# GTU-2-V1_1-20160516.net
KiCad netlist of a schematic drawn in Altium Designer
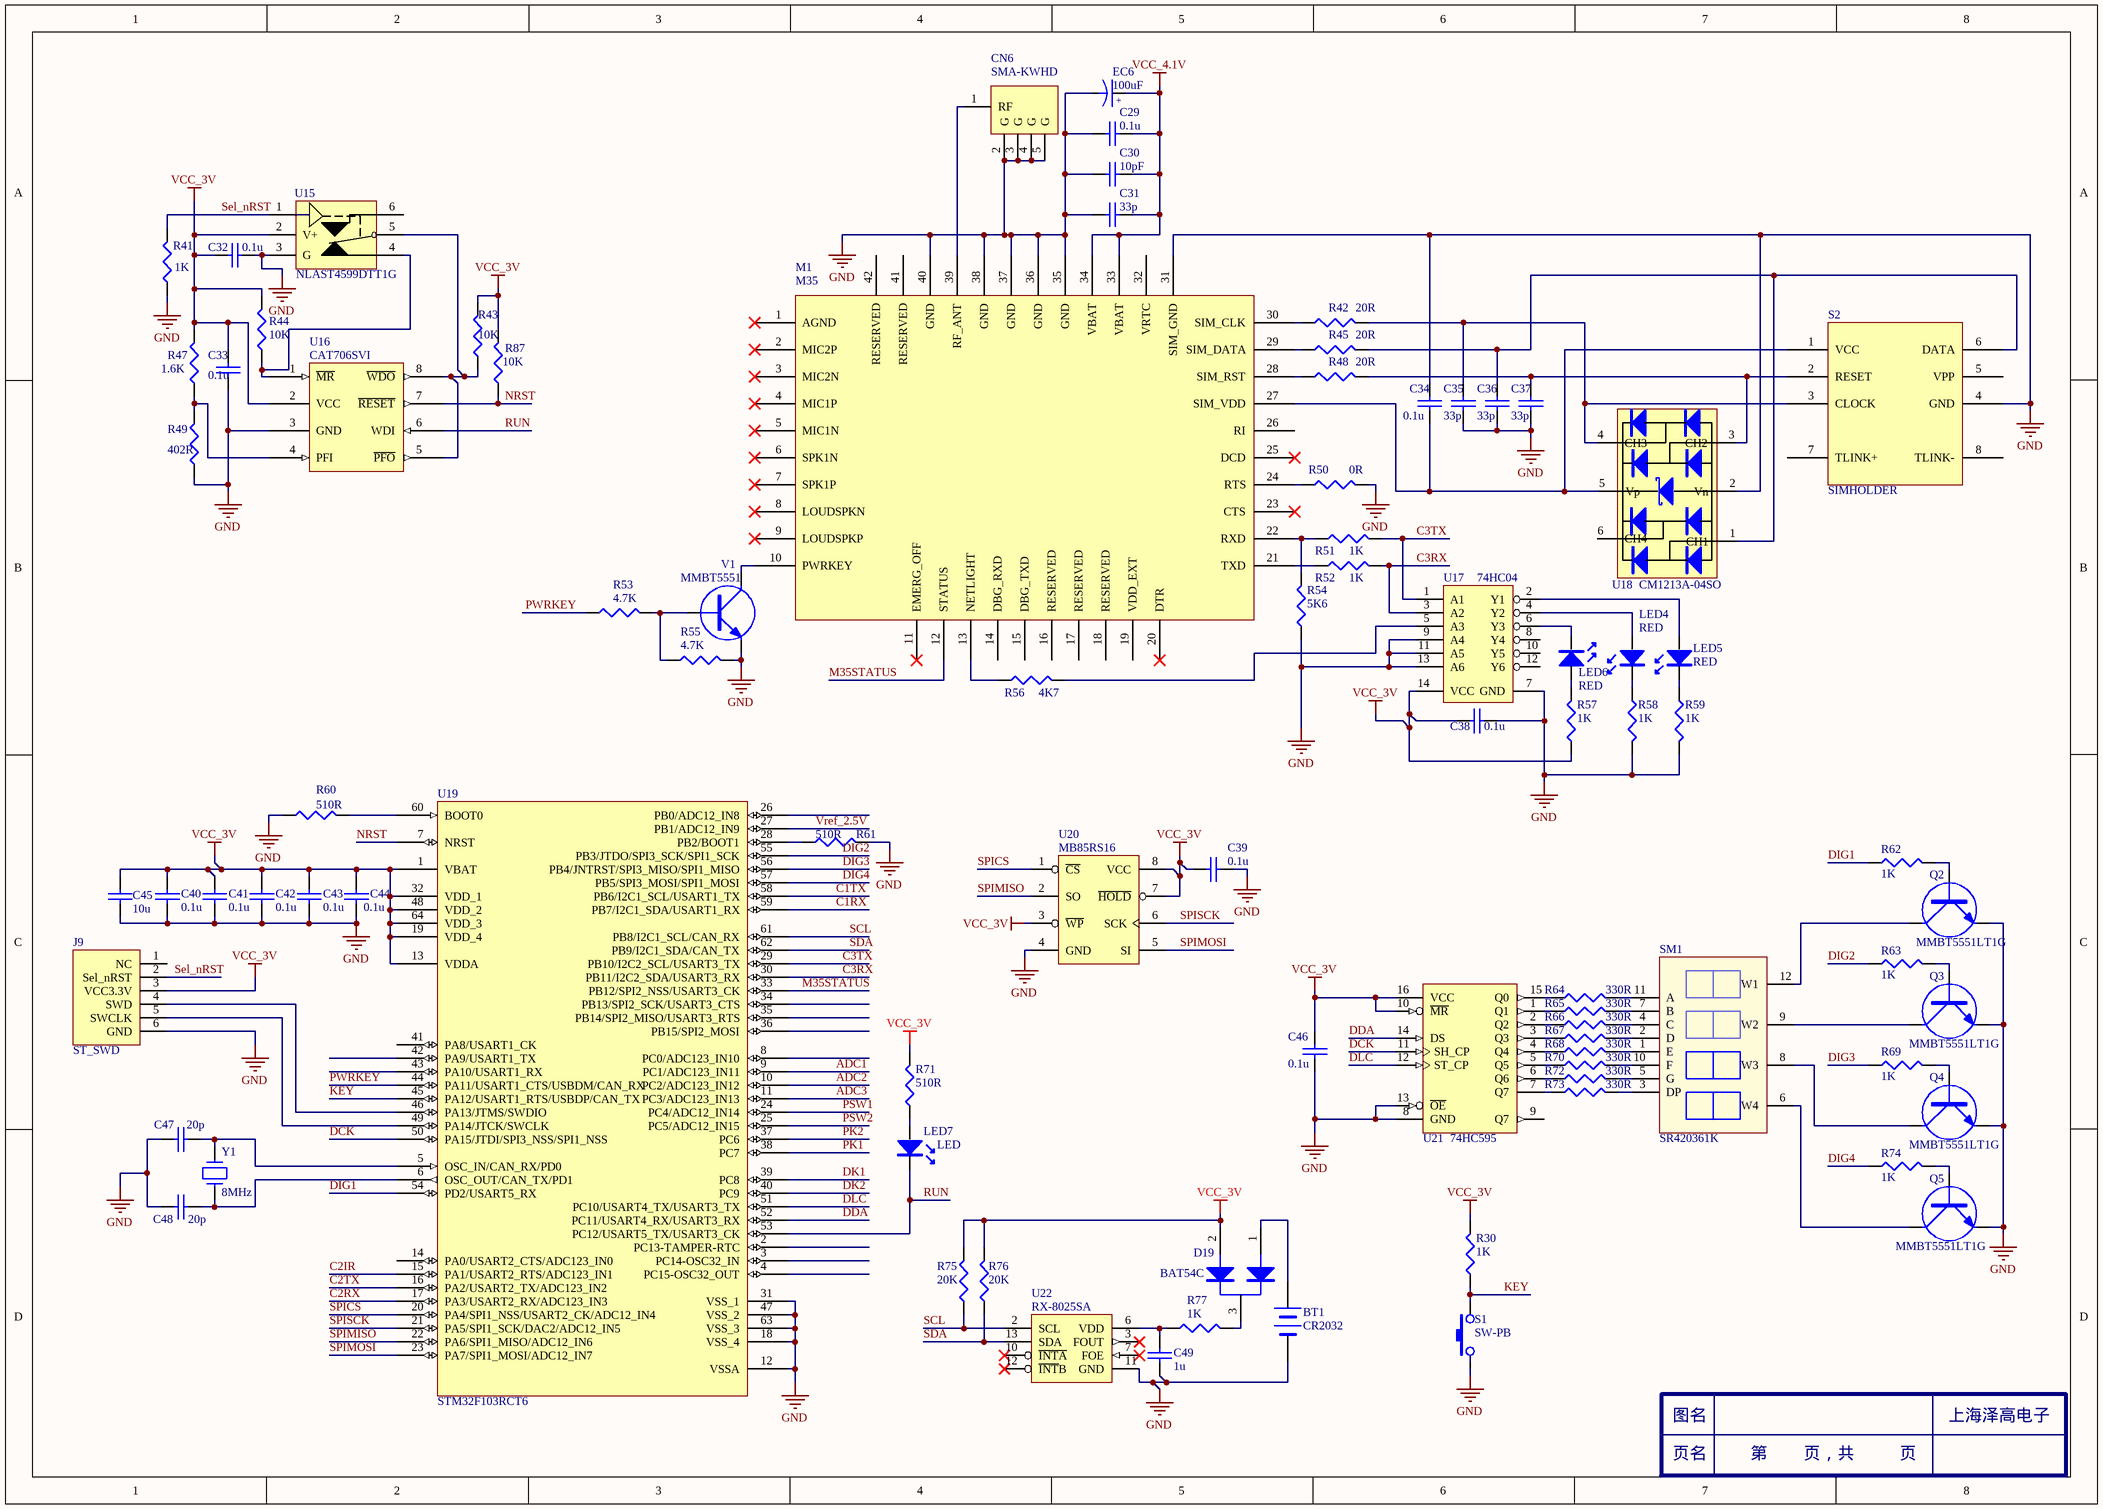
[diagram p0: GTU-2-V1.1-20160516.SCHDOC]

(export (version "E")
  (design (tool "Eeschema 10.0.6"))
  (components
    (comp (ref "4") (value "Component_1") (libsource (lib "*") (part "Component_1")))
    (comp (ref "BT1")
      (value "CR2032")
      (footprint "CR2032")
      (description "Battery")
      (libsource (lib "*") (part "BATTERY"))
    )
    (comp (ref "C29")
      (value "0.1u")
      (footprint "0805-C")
      (description "Capacitor")
      (libsource (lib "STSCH-2014-01-20    ") (part "CAP"))
    )
    (comp (ref "C30")
      (value "10pF")
      (footprint "0805-C")
      (description "Capacitor")
      (libsource (lib "STSCH-2014-01-20    ") (part "CAP"))
    )
    (comp (ref "C31")
      (value "33p")
      (footprint "0805-C")
      (description "Capacitor")
      (libsource (lib "STSCH-2014-01-20    ") (part "CAP"))
    )
    (comp (ref "C32")
      (value "0.1u")
      (footprint "0805-C")
      (description "Capacitor")
      (fields (field (name "MFG") "TDK"))
      (libsource (lib "SCHLIB-ZG-2015.12.11      ") (part "CAP"))
    )
    (comp (ref "C33")
      (value "0.1u")
      (footprint "0805-C")
      (description "Capacitor")
      (libsource (lib "STSCH-2011-12-16") (part "CAP"))
    )
    (comp (ref "C34")
      (value "0.1u")
      (footprint "0805-C")
      (description "Capacitor")
      (libsource (lib "STSCH-2014-01-20    ") (part "CAP"))
    )
    (comp (ref "C35")
      (value "33p")
      (footprint "0805-C")
      (description "Capacitor")
      (libsource (lib "STSCH-2014-01-20    ") (part "CAP"))
    )
    (comp (ref "C36")
      (value "33p")
      (footprint "0805-C")
      (description "Capacitor")
      (libsource (lib "STSCH-2014-01-20    ") (part "CAP"))
    )
    (comp (ref "C37")
      (value "33p")
      (footprint "0805-C")
      (description "Capacitor")
      (libsource (lib "STSCH-2014-01-20    ") (part "CAP"))
    )
    (comp (ref "C38")
      (value "0.1u")
      (footprint "0805-C")
      (description "Capacitor")
      (libsource (lib "STSCH-2013-02-22   ") (part "CAP"))
    )
    (comp (ref "C39")
      (value "0.1u")
      (footprint "0805-C")
      (description "Capacitor")
      (libsource (lib "STSCH-2013-02-22   ") (part "CAP"))
    )
    (comp (ref "C40")
      (value "0.1u")
      (footprint "0805-C")
      (description "Capacitor")
      (libsource (lib "*") (part "CAP"))
    )
    (comp (ref "C41")
      (value "0.1u")
      (footprint "0805-C")
      (description "Capacitor")
      (libsource (lib "*") (part "CAP"))
    )
    (comp (ref "C42")
      (value "0.1u")
      (footprint "0805-C")
      (description "Capacitor")
      (libsource (lib "*") (part "CAP"))
    )
    (comp (ref "C43")
      (value "0.1u")
      (footprint "0805-C")
      (description "Capacitor")
      (libsource (lib "*") (part "CAP"))
    )
    (comp (ref "C44")
      (value "0.1u")
      (footprint "0805-C")
      (description "Capacitor")
      (libsource (lib "*") (part "CAP"))
    )
    (comp (ref "C45")
      (value "10u")
      (footprint "0805-C")
      (description "Capacitor")
      (libsource (lib "*") (part "CAP"))
    )
    (comp (ref "C46")
      (value "0.1u")
      (footprint "0805-C")
      (description "Capacitor")
      (libsource (lib "STSCH-2013-02-22   ") (part "CAP"))
    )
    (comp (ref "C47")
      (value "20p")
      (footprint "0805-C")
      (description "Capacitor")
      (libsource (lib "*") (part "CAP"))
    )
    (comp (ref "C48")
      (value "20p")
      (footprint "0805-C")
      (description "Capacitor")
      (libsource (lib "*") (part "CAP"))
    )
    (comp (ref "C49")
      (value "1u")
      (footprint "0805-C")
      (description "Capacitor")
      (libsource (lib "") (part "CAP_1"))
    )
    (comp (ref "CN6")
      (value "SMA-KWHD")
      (footprint "SMA-KWHD")
      (description "RF插座")
      (libsource (lib "STSCH-2014-02-13    ") (part "SMA-KWHD"))
    )
    (comp (ref "D19") (value "BAT54C") (footprint "BAT54S/SOT-23") (libsource (lib "*") (part "BAT54C")))
    (comp (ref "EC6")
      (value "100uF")
      (footprint "7361-V")
      (libsource (lib "STSCH-2014-01-20    ") (part "CAP Tan"))
    )
    (comp (ref "J9")
      (value "ST_SWD")
      (footprint "SWD_DOWNLOAD")
      (description "STM32 SWD调试端口")
      (libsource (lib "SCHLIB-ZG-2015.12.11      ") (part "ST_SWD"))
    )
    (comp (ref "LED4")
      (value "RED")
      (footprint "0805-LED")
      (libsource (lib "STSCH-2012-11-26   ") (part "LED"))
    )
    (comp (ref "LED5")
      (value "RED")
      (footprint "0805-LED")
      (libsource (lib "STSCH-2012-11-26   ") (part "LED"))
    )
    (comp (ref "LED6")
      (value "RED")
      (footprint "0805-LED")
      (libsource (lib "STSCH-2012-11-26   ") (part "LED"))
    )
    (comp (ref "LED7") (value "LED") (footprint "0805-LED") (libsource (lib "STSCH-20110618") (part "LED")))
    (comp (ref "M1") (value "M35") (footprint "M35") (libsource (lib "STSCH-2014-01-20    ") (part "M35")))
    (comp (ref "Q2")
      (value "MMBT5551")
      (footprint "SOT-23")
      (description "NPN Transistor 160V 0.6A")
      (fields (field (name "MFG") "DIODES") (field (name "MFG2-PN") "MMBT5551LT1G"))
      (libsource (lib "SCHLIB-ZG-2016.01.18      ") (part "MMBT5551"))
    )
    (comp (ref "Q3")
      (value "MMBT5551")
      (footprint "SOT-23")
      (description "NPN Transistor 160V 0.6A")
      (fields (field (name "MFG") "DIODES") (field (name "MFG2-PN") "MMBT5551LT1G"))
      (libsource (lib "SCHLIB-ZG-2016.01.18      ") (part "MMBT5551"))
    )
    (comp (ref "Q4")
      (value "MMBT5551")
      (footprint "SOT-23")
      (description "NPN Transistor 160V 0.6A")
      (fields (field (name "MFG") "DIODES") (field (name "MFG2-PN") "MMBT5551LT1G"))
      (libsource (lib "SCHLIB-ZG-2016.01.18      ") (part "MMBT5551"))
    )
    (comp (ref "Q5")
      (value "MMBT5551")
      (footprint "SOT-23")
      (description "NPN Transistor 160V 0.6A")
      (fields (field (name "MFG") "DIODES") (field (name "MFG2-PN") "MMBT5551LT1G"))
      (libsource (lib "SCHLIB-ZG-2016.01.18      ") (part "MMBT5551"))
    )
    (comp (ref "R30") (value "1K") (footprint "0805-R") (libsource (lib "STSCH-2014-03-27    ") (part "RES")))
    (comp (ref "R41")
      (value "1K")
      (footprint "0805-R")
      (description "电阻")
      (fields (field (name "MFG") "YAGO") (field (name "Comment") "RES"))
      (libsource (lib "SCHLIB-ZG-2015.12.11      ") (part "RES"))
    )
    (comp (ref "R42")
      (value "20R")
      (footprint "0805-R")
      (libsource (lib "STSCH-2014-01-20    ") (part "RES"))
    )
    (comp (ref "R43") (value "10K") (footprint "0805-R") (libsource (lib "") (part "RES_1")))
    (comp (ref "R44") (value "10K") (footprint "0805-R") (libsource (lib "") (part "RES_1")))
    (comp (ref "R45")
      (value "20R")
      (footprint "0805-R")
      (libsource (lib "STSCH-2014-01-20    ") (part "RES"))
    )
    (comp (ref "R47")
      (value "1.6K")
      (footprint "0805-R")
      (description "电阻")
      (fields (field (name "MFG") "YAGO"))
      (libsource (lib "SCHLIB-ZG-2015.12.11      ") (part "RES"))
    )
    (comp (ref "R48")
      (value "20R")
      (footprint "0805-R")
      (libsource (lib "STSCH-2014-01-20    ") (part "RES"))
    )
    (comp (ref "R49")
      (value "402R")
      (footprint "0805-R")
      (description "电阻")
      (fields (field (name "MFG") "YAGO"))
      (libsource (lib "SCHLIB-ZG-2015.12.11      ") (part "RES"))
    )
    (comp (ref "R50") (value "0R") (footprint "0805-R") (libsource (lib "STSCH-2014-01-20    ") (part "RES")))
    (comp (ref "R51") (value "1K") (footprint "0805-R") (libsource (lib "STSCH-2014-01-20    ") (part "RES")))
    (comp (ref "R52") (value "1K") (footprint "0805-R") (libsource (lib "STSCH-2014-01-20    ") (part "RES")))
    (comp (ref "R53")
      (value "4.7K")
      (footprint "0805-R")
      (libsource (lib "STSCH-2014-01-20    ") (part "RES"))
    )
    (comp (ref "R54")
      (value "5K6")
      (footprint "0805-R")
      (libsource (lib "STSCH-2014-01-20    ") (part "RES"))
    )
    (comp (ref "R55")
      (value "4.7K")
      (footprint "0805-R")
      (libsource (lib "STSCH-2014-01-20    ") (part "RES"))
    )
    (comp (ref "R56")
      (value "4K7")
      (footprint "0805-R")
      (libsource (lib "STSCH-2014-02-12    ") (part "RES"))
    )
    (comp (ref "R57") (value "1K") (footprint "0805-R") (libsource (lib "STSCH-2012-11-26   ") (part "RES")))
    (comp (ref "R58") (value "1K") (footprint "0805-R") (libsource (lib "STSCH-2012-11-26   ") (part "RES")))
    (comp (ref "R59") (value "1K") (footprint "0805-R") (libsource (lib "STSCH-2012-11-26   ") (part "RES")))
    (comp (ref "R60") (value "510R") (footprint "0805-R") (libsource (lib "") (part "RES_1")))
    (comp (ref "R61") (value "510R") (footprint "0805-R") (libsource (lib "") (part "RES_1")))
    (comp (ref "R62")
      (value "1K")
      (footprint "0805-R")
      (description "电阻")
      (fields (field (name "MFG") "YAGO") (field (name "Comment") "RES"))
      (libsource (lib "SCHLIB-ZG-2016.01.18      ") (part "RES"))
    )
    (comp (ref "R63")
      (value "1K")
      (footprint "0805-R")
      (description "电阻")
      (fields (field (name "MFG") "YAGO") (field (name "Comment") "RES"))
      (libsource (lib "SCHLIB-ZG-2016.01.18      ") (part "RES"))
    )
    (comp (ref "R64") (value "330R") (footprint "0805-R") (libsource (lib "*") (part "RES")))
    (comp (ref "R65") (value "330R") (footprint "0805-R") (libsource (lib "*") (part "RES")))
    (comp (ref "R66") (value "330R") (footprint "0805-R") (libsource (lib "*") (part "RES")))
    (comp (ref "R67") (value "330R") (footprint "0805-R") (libsource (lib "*") (part "RES")))
    (comp (ref "R68") (value "330R") (footprint "0805-R") (libsource (lib "*") (part "RES")))
    (comp (ref "R69")
      (value "1K")
      (footprint "0805-R")
      (description "电阻")
      (fields (field (name "MFG") "YAGO") (field (name "Comment") "RES"))
      (libsource (lib "SCHLIB-ZG-2016.01.18      ") (part "RES"))
    )
    (comp (ref "R70") (value "330R") (footprint "0805-R") (libsource (lib "*") (part "RES")))
    (comp (ref "R71") (value "510R") (footprint "0805-R") (libsource (lib "STSCH-20110618") (part "RES")))
    (comp (ref "R72") (value "330R") (footprint "0805-R") (libsource (lib "*") (part "RES")))
    (comp (ref "R73") (value "330R") (footprint "0805-R") (libsource (lib "*") (part "RES")))
    (comp (ref "R74")
      (value "1K")
      (footprint "0805-R")
      (description "电阻")
      (fields (field (name "MFG") "YAGO") (field (name "Comment") "RES"))
      (libsource (lib "SCHLIB-ZG-2016.01.18      ") (part "RES"))
    )
    (comp (ref "R75") (value "20K") (footprint "0805-R") (libsource (lib "*") (part "RES")))
    (comp (ref "R76") (value "20K") (footprint "0805-R") (libsource (lib "*") (part "RES")))
    (comp (ref "R77") (value "1K") (footprint "0805-R") (libsource (lib "STSCH-2013-08-08    ") (part "RES")))
    (comp (ref "R87") (value "10K") (footprint "0805-R") (libsource (lib "") (part "RES_1")))
    (comp (ref "S1")
      (value "SW-PB")
      (footprint "JMP")
      (description "轻触按钮")
      (libsource (lib "STSCH-2014-03-27    ") (part "SW-PB"))
    )
    (comp (ref "S2")
      (value "SIMHOLDER")
      (footprint "SIM-HOLDER")
      (libsource (lib "STSCH-2014-01-20    ") (part "SIMHOLDER"))
    )
    (comp (ref "SM1")
      (value "SR420361K")
      (footprint "SR420361")
      (description "共阴极0.28寸4位数码管品牌ARK")
      (libsource (lib "SCHLIB-ZG-2016.01.18      ") (part "SR420361"))
    )
    (comp (ref "U15")
      (value "NLAST4599DTT1G")
      (footprint "SOT-23-6")
      (libsource (lib "轨旁检测-20151210") (part "NLAST4599DTT1G"))
    )
    (comp (ref "U16") (value "CAT706SVI") (footprint "SO-8") (libsource (lib "*") (part "SP706T")))
    (comp (ref "U17")
      (value "74HC04")
      (footprint "SO-14")
      (libsource (lib "STSCH-2014-05-18     ") (part "74HC04"))
    )
    (comp (ref "U18")
      (value "CM1213A-04SO")
      (footprint "SOT-23-6")
      (libsource (lib "STSCH-2015.09.30  ") (part "CM1213A-04SO"))
    )
    (comp (ref "U19")
      (value "STM32F103RCT6")
      (footprint "LQFP-64")
      (libsource (lib "STSCH-2014-01-15") (part "STM32F103RCT6"))
    )
    (comp (ref "U20")
      (value "MB85RS16")
      (footprint "SO-8")
      (libsource (lib "STSCH-2013-02-22   ") (part "FM25256B"))
    )
    (comp (ref "U21")
      (value "74HC595")
      (footprint "SO-16")
      (description "8位移位寄存器")
      (fields (field (name "MFG") "NXP"))
      (libsource (lib "SCHLIB-ZG-2016.01.18      ") (part "74HC595"))
    )
    (comp (ref "U22") (value "RX-8025SA") (footprint "SO-14") (libsource (lib "*") (part "RX-8025SA")))
    (comp (ref "V1")
      (value "MMBT5551")
      (footprint "SOT-23")
      (description "贴片NPN")
      (libsource (lib "STSCH-2014-01-20    ") (part "MMBT5551"))
    )
    (comp (ref "Y1")
      (value "8MHz")
      (footprint "SM-49")
      (description "Crystal")
      (libsource (lib "*") (part "CRYSTAL"))
    )
  )
  (nets
    (net (code "1") (name "/ADC1") (class "Default")
      (node (ref "U19") (pin "9") (pinfunction "PC1/ADC123_IN11_9") (pintype "bidirectional"))
    )
    (net (code "2") (name "/ADC2") (class "Default")
      (node (ref "U19") (pin "10") (pinfunction "PC2/ADC123_IN12_10") (pintype "bidirectional"))
    )
    (net (code "3") (name "/ADC3") (class "Default")
      (node (ref "U19") (pin "11") (pinfunction "PC3/ADC123_IN13_11") (pintype "bidirectional"))
    )
    (net (code "4") (name "/C1RX") (class "Default")
      (node (ref "U19") (pin "59") (pinfunction "PB7/I2C1_SDA/USART1_RX_59") (pintype "bidirectional"))
    )
    (net (code "5") (name "/C1TX") (class "Default")
      (node (ref "U19") (pin "58") (pinfunction "PB6/I2C1_SCL/USART1_TX_58") (pintype "bidirectional"))
    )
    (net (code "6") (name "/C2IR") (class "Default")
      (node (ref "U19") (pin "15") (pinfunction "PA1/USART2_RTS/ADC123_IN1_15") (pintype "bidirectional"))
    )
    (net (code "7") (name "/C2RX") (class "Default")
      (node (ref "U19") (pin "17") (pinfunction "PA3/USART2_RX/ADC123_IN3_17") (pintype "bidirectional"))
    )
    (net (code "8") (name "/C2TX") (class "Default")
      (node (ref "U19") (pin "16") (pinfunction "PA2/USART2_TX/ADC123_IN2_16") (pintype "bidirectional"))
    )
    (net (code "9") (name "/C3RX") (class "Default")
      (node (ref "R52") (pin "2") (pinfunction "2_2") (pintype "passive"))
      (node (ref "U17") (pin "3") (pinfunction "A2_3") (pintype "passive"))
      (node (ref "U19") (pin "30") (pinfunction "PB11/I2C2_SDA/USART3_RX_30") (pintype "bidirectional"))
    )
    (net (code "10") (name "/C3TX") (class "Default")
      (node (ref "R51") (pin "2") (pinfunction "2_2") (pintype "passive"))
      (node (ref "U17") (pin "1") (pinfunction "A1_1") (pintype "passive"))
      (node (ref "U19") (pin "29") (pinfunction "PB10/I2C2_SCL/USART3_TX_29") (pintype "bidirectional"))
    )
    (net (code "11") (name "/DCK") (class "Default")
      (node (ref "U19") (pin "50") (pinfunction "PA15/JTDI/SPI3_NSS/SPI1_NSS_50") (pintype "bidirectional"))
      (node (ref "U21") (pin "11") (pinfunction "SH_CP_11") (pintype "input"))
    )
    (net (code "12") (name "/DDA") (class "Default")
      (node (ref "U19") (pin "52") (pinfunction "PC11/USART4_RX/USART3_RX_52") (pintype "bidirectional"))
      (node (ref "U21") (pin "14") (pinfunction "DS_14") (pintype "input"))
    )
    (net (code "13") (name "/DIG1") (class "Default")
      (node (ref "R62") (pin "1") (pinfunction "1_1") (pintype "passive"))
      (node (ref "U19") (pin "54") (pinfunction "PD2/USART5_RX_54") (pintype "bidirectional"))
    )
    (net (code "14") (name "/DIG2") (class "Default")
      (node (ref "R63") (pin "1") (pinfunction "1_1") (pintype "passive"))
      (node (ref "U19") (pin "55") (pinfunction "PB3/JTDO/SPI3_SCK/SPI1_SCK_55") (pintype "bidirectional"))
    )
    (net (code "15") (name "/DIG3") (class "Default")
      (node (ref "R69") (pin "1") (pinfunction "1_1") (pintype "passive"))
      (node (ref "U19") (pin "56") (pinfunction "PB4/JNTRST/SPI3_MISO/SPI1_MISO_56") (pintype "bidirectional"))
    )
    (net (code "16") (name "/DIG4") (class "Default")
      (node (ref "R74") (pin "1") (pinfunction "1_1") (pintype "passive"))
      (node (ref "U19") (pin "57") (pinfunction "PB5/SPI3_MOSI/SPI1_MOSI_57") (pintype "bidirectional"))
    )
    (net (code "17") (name "/DK1") (class "Default")
      (node (ref "U19") (pin "39") (pinfunction "PC8_39") (pintype "bidirectional"))
    )
    (net (code "18") (name "/DK2") (class "Default")
      (node (ref "U19") (pin "40") (pinfunction "PC9_40") (pintype "bidirectional"))
    )
    (net (code "19") (name "/DLC") (class "Default")
      (node (ref "U19") (pin "51") (pinfunction "PC10/USART4_TX/USART3_TX_51") (pintype "bidirectional"))
      (node (ref "U21") (pin "12") (pinfunction "ST_CP_12") (pintype "input"))
    )
    (net (code "20") (name "/KEY") (class "Default")
      (node (ref "R30") (pin "1") (pinfunction "1_1") (pintype "passive"))
      (node (ref "S1") (pin "2") (pinfunction "2_2") (pintype "passive"))
      (node (ref "U19") (pin "45") (pinfunction "PA12/USART1_RTS/USBDP/CAN_TX_45") (pintype "bidirectional"))
    )
    (net (code "21") (name "/M35STATUS") (class "Default")
      (node (ref "M1") (pin "12") (pinfunction "STATUS_12") (pintype "passive"))
      (node (ref "U19") (pin "33") (pinfunction "PB12/SPI2_NSS/USART3_CK_33") (pintype "bidirectional"))
    )
    (net (code "22") (name "/NRST") (class "Default")
      (node (ref "R87") (pin "1") (pinfunction "1_1") (pintype "passive"))
      (node (ref "U16") (pin "7") (pinfunction "~{RESET}_7") (pintype "output"))
      (node (ref "U19") (pin "7") (pinfunction "NRST_7") (pintype "bidirectional"))
    )
    (net (code "23") (name "/PK1") (class "Default")
      (node (ref "U19") (pin "38") (pinfunction "PC7_38") (pintype "bidirectional"))
    )
    (net (code "24") (name "/PK2") (class "Default")
      (node (ref "U19") (pin "37") (pinfunction "PC6_37") (pintype "bidirectional"))
    )
    (net (code "25") (name "/PSW1") (class "Default")
      (node (ref "U19") (pin "24") (pinfunction "PC4/ADC12_IN14_24") (pintype "bidirectional"))
    )
    (net (code "26") (name "/PSW2") (class "Default")
      (node (ref "U19") (pin "25") (pinfunction "PC5/ADC12_IN15_25") (pintype "bidirectional"))
    )
    (net (code "27") (name "/PWRKEY") (class "Default")
      (node (ref "R53") (pin "1") (pinfunction "1_1") (pintype "passive"))
      (node (ref "U19") (pin "44") (pinfunction "PA11/USART1_CTS/USBDM/CAN_RX_44") (pintype "bidirectional"))
    )
    (net (code "28") (name "/RUN") (class "Default")
      (node (ref "LED7") (pin "2") (pintype "passive"))
      (node (ref "U16") (pin "6") (pinfunction "WDI_6") (pintype "input"))
      (node (ref "U19") (pin "53") (pinfunction "PC12/USART5_TX/USART3_CK_53") (pintype "bidirectional"))
    )
    (net (code "29") (name "/SCL") (class "Default")
      (node (ref "R75") (pin "1") (pinfunction "1_1") (pintype "passive"))
      (node (ref "U19") (pin "61") (pinfunction "PB8/I2C1_SCL/CAN_RX_61") (pintype "bidirectional"))
      (node (ref "U22") (pin "2") (pinfunction "SCL_2") (pintype "open_collector"))
    )
    (net (code "30") (name "/SDA") (class "Default")
      (node (ref "R76") (pin "1") (pinfunction "1_1") (pintype "passive"))
      (node (ref "U19") (pin "62") (pinfunction "PB9/I2C1_SDA/CAN_TX_62") (pintype "bidirectional"))
      (node (ref "U22") (pin "13") (pinfunction "SDA_13") (pintype "passive"))
    )
    (net (code "31") (name "/SPICS") (class "Default")
      (node (ref "U19") (pin "20") (pinfunction "PA4/SPI1_NSS/USART2_CK/ADC12_IN4_20") (pintype "bidirectional"))
      (node (ref "U20") (pin "1") (pinfunction "~{CS}_1") (pintype "passive"))
    )
    (net (code "32") (name "/SPIMISO") (class "Default")
      (node (ref "U19") (pin "22") (pinfunction "PA6/SPI1_MISO/ADC12_IN6_22") (pintype "bidirectional"))
      (node (ref "U20") (pin "2") (pinfunction "SO_2") (pintype "passive"))
    )
    (net (code "33") (name "/SPIMOSI") (class "Default")
      (node (ref "U19") (pin "23") (pinfunction "PA7/SPI1_MOSI/ADC12_IN7_23") (pintype "bidirectional"))
      (node (ref "U20") (pin "5") (pinfunction "SI_5") (pintype "passive"))
    )
    (net (code "34") (name "/SPISCK") (class "Default")
      (node (ref "U19") (pin "21") (pinfunction "PA5/SPI1_SCK/DAC2/ADC12_IN5_21") (pintype "bidirectional"))
      (node (ref "U20") (pin "6") (pinfunction "SCK_6") (pintype "passive"))
    )
    (net (code "35") (name "/Sel_nRST") (class "Default")
      (node (ref "J9") (pin "2") (pinfunction "Sel_nRST_2") (pintype "passive"))
      (node (ref "R41") (pin "2") (pinfunction "2_2") (pintype "passive"))
      (node (ref "U15") (pin "1") (pinfunction "SELECT_1") (pintype "passive"))
    )
    (net (code "36") (name "/Vref_2.5V") (class "Default")
      (node (ref "U19") (pin "27") (pinfunction "PB1/ADC12_IN9_27") (pintype "bidirectional"))
    )
    (net (code "37") (name "GND") (class "Default")
      (node (ref "BT1") (pin "2") (pinfunction "-_2") (pintype "passive"))
      (node (ref "C29") (pin "2") (pinfunction "2_2") (pintype "passive"))
      (node (ref "C30") (pin "2") (pinfunction "2_2") (pintype "passive"))
      (node (ref "C31") (pin "2") (pinfunction "2_2") (pintype "passive"))
      (node (ref "C32") (pin "2") (pinfunction "2_2") (pintype "passive"))
      (node (ref "C33") (pin "2") (pinfunction "2_2") (pintype "passive"))
      (node (ref "C34") (pin "1") (pinfunction "1_1") (pintype "passive"))
      (node (ref "C35") (pin "2") (pinfunction "2_2") (pintype "passive"))
      (node (ref "C36") (pin "2") (pinfunction "2_2") (pintype "passive"))
      (node (ref "C37") (pin "2") (pinfunction "2_2") (pintype "passive"))
      (node (ref "C38") (pin "2") (pinfunction "2_2") (pintype "passive"))
      (node (ref "C39") (pin "2") (pinfunction "2_2") (pintype "passive"))
      (node (ref "C40") (pin "2") (pinfunction "2_2") (pintype "passive"))
      (node (ref "C41") (pin "2") (pinfunction "2_2") (pintype "passive"))
      (node (ref "C42") (pin "2") (pinfunction "2_2") (pintype "passive"))
      (node (ref "C43") (pin "2") (pinfunction "2_2") (pintype "passive"))
      (node (ref "C44") (pin "2") (pinfunction "2_2") (pintype "passive"))
      (node (ref "C45") (pin "2") (pinfunction "2_2") (pintype "passive"))
      (node (ref "C46") (pin "2") (pinfunction "2_2") (pintype "passive"))
      (node (ref "C47") (pin "2") (pinfunction "2_2") (pintype "passive"))
      (node (ref "C48") (pin "2") (pinfunction "2_2") (pintype "passive"))
      (node (ref "C49") (pin "2") (pinfunction "2_2") (pintype "passive"))
      (node (ref "CN6") (pin "2") (pinfunction "G_2") (pintype "passive"))
      (node (ref "CN6") (pin "3") (pinfunction "G_3") (pintype "passive"))
      (node (ref "CN6") (pin "4") (pinfunction "G_4") (pintype "passive"))
      (node (ref "CN6") (pin "5") (pinfunction "G_5") (pintype "passive"))
      (node (ref "EC6") (pin "2") (pinfunction "2_2") (pintype "passive"))
      (node (ref "J9") (pin "6") (pinfunction "GND_6") (pintype "passive"))
      (node (ref "M1") (pin "31") (pinfunction "SIM_GND_31") (pintype "passive"))
      (node (ref "M1") (pin "35") (pinfunction "GND_35") (pintype "passive"))
      (node (ref "M1") (pin "36") (pinfunction "GND_36") (pintype "passive"))
      (node (ref "M1") (pin "37") (pinfunction "GND_37") (pintype "passive"))
      (node (ref "M1") (pin "38") (pinfunction "GND_38") (pintype "passive"))
      (node (ref "M1") (pin "40") (pinfunction "GND_40") (pintype "passive"))
      (node (ref "Q2") (pin "2") (pinfunction "E_2") (pintype "passive"))
      (node (ref "Q3") (pin "2") (pinfunction "E_2") (pintype "passive"))
      (node (ref "Q4") (pin "2") (pinfunction "E_2") (pintype "passive"))
      (node (ref "Q5") (pin "2") (pinfunction "E_2") (pintype "passive"))
      (node (ref "R41") (pin "1") (pinfunction "1_1") (pintype "passive"))
      (node (ref "R49") (pin "1") (pinfunction "1_1") (pintype "passive"))
      (node (ref "R50") (pin "2") (pinfunction "2_2") (pintype "passive"))
      (node (ref "R54") (pin "1") (pinfunction "1_1") (pintype "passive"))
      (node (ref "R55") (pin "2") (pinfunction "2_2") (pintype "passive"))
      (node (ref "R58") (pin "2") (pinfunction "2_2") (pintype "passive"))
      (node (ref "R59") (pin "2") (pinfunction "2_2") (pintype "passive"))
      (node (ref "R60") (pin "1") (pinfunction "1_1") (pintype "passive"))
      (node (ref "R61") (pin "2") (pinfunction "2_2") (pintype "passive"))
      (node (ref "S1") (pin "1") (pinfunction "1_1") (pintype "passive"))
      (node (ref "S2") (pin "4") (pinfunction "GND_4") (pintype "passive"))
      (node (ref "U15") (pin "3") (pinfunction "G_3") (pintype "passive"))
      (node (ref "U16") (pin "3") (pinfunction "GND_3") (pintype "power_in"))
      (node (ref "U17") (pin "11") (pinfunction "A5_11") (pintype "passive"))
      (node (ref "U17") (pin "13") (pinfunction "A6_13") (pintype "passive"))
      (node (ref "U17") (pin "7") (pinfunction "GND_7") (pintype "passive"))
      (node (ref "U17") (pin "9") (pinfunction "A4_9") (pintype "passive"))
      (node (ref "U18") (pin "2") (pinfunction "Vn_2") (pintype "passive"))
      (node (ref "U19") (pin "12") (pinfunction "VSSA_12") (pintype "power_in"))
      (node (ref "U19") (pin "18") (pinfunction "VSS_4_18") (pintype "power_in"))
      (node (ref "U19") (pin "31") (pinfunction "VSS_1_31") (pintype "power_in"))
      (node (ref "U19") (pin "47") (pinfunction "VSS_2_47") (pintype "power_in"))
      (node (ref "U19") (pin "63") (pinfunction "VSS_3_63") (pintype "power_in"))
      (node (ref "U20") (pin "4") (pinfunction "GND_4") (pintype "passive"))
      (node (ref "U21") (pin "13") (pinfunction "~{OE}_13") (pintype "input"))
      (node (ref "U21") (pin "8") (pinfunction "GND_8") (pintype "power_in"))
      (node (ref "U22") (pin "11") (pinfunction "GND_11") (pintype "power_in"))
      (node (ref "V1") (pin "2") (pinfunction "E_2") (pintype "passive"))
    )
    (net (code "38") (name "Net-(BT1-+)") (class "Default")
      (node (ref "BT1") (pin "1") (pinfunction "+_1") (pintype "passive"))
      (node (ref "D19") (pin "1") (pintype "passive"))
    )
    (net (code "39") (name "Net-(CN6-RF)") (class "Default")
      (node (ref "CN6") (pin "1") (pinfunction "RF_1") (pintype "passive"))
      (node (ref "M1") (pin "39") (pinfunction "RF_ANT_39") (pintype "passive"))
    )
    (net (code "40") (name "Net-(D19-Pad3)") (class "Default")
      (node (ref "D19") (pin "3") (pintype "passive"))
      (node (ref "R77") (pin "2") (pinfunction "2_2") (pintype "passive"))
    )
    (net (code "41") (name "Net-(J9-SWCLK)") (class "Default")
      (node (ref "J9") (pin "5") (pinfunction "SWCLK_5") (pintype "passive"))
      (node (ref "U19") (pin "49") (pinfunction "PA14/JTCK/SWCLK_49") (pintype "bidirectional"))
    )
    (net (code "42") (name "Net-(J9-SWD)") (class "Default")
      (node (ref "J9") (pin "4") (pinfunction "SWD_4") (pintype "passive"))
      (node (ref "U19") (pin "46") (pinfunction "PA13/JTMS/SWDIO_46") (pintype "bidirectional"))
    )
    (net (code "43") (name "Net-(LED4-Pad2)") (class "Default")
      (node (ref "LED4") (pin "2") (pintype "passive"))
      (node (ref "R58") (pin "1") (pinfunction "1_1") (pintype "passive"))
    )
    (net (code "44") (name "Net-(LED5-Pad2)") (class "Default")
      (node (ref "LED5") (pin "2") (pintype "passive"))
      (node (ref "R59") (pin "1") (pinfunction "1_1") (pintype "passive"))
    )
    (net (code "45") (name "Net-(LED6-Pad1)") (class "Default")
      (node (ref "LED6") (pin "1") (pintype "passive"))
      (node (ref "R57") (pin "2") (pinfunction "2_2") (pintype "passive"))
    )
    (net (code "46") (name "Net-(LED7-Pad1)") (class "Default")
      (node (ref "LED7") (pin "1") (pintype "passive"))
      (node (ref "R71") (pin "1") (pinfunction "1_1") (pintype "passive"))
    )
    (net (code "47") (name "Net-(M1-NETLIGHT)") (class "Default")
      (node (ref "M1") (pin "13") (pinfunction "NETLIGHT_13") (pintype "passive"))
      (node (ref "R56") (pin "1") (pinfunction "1_1") (pintype "passive"))
    )
    (net (code "48") (name "Net-(M1-PWRKEY)") (class "Default")
      (node (ref "M1") (pin "10") (pinfunction "PWRKEY_10") (pintype "passive"))
      (node (ref "V1") (pin "3") (pinfunction "C_3") (pintype "passive"))
    )
    (net (code "49") (name "Net-(M1-RTS)") (class "Default")
      (node (ref "M1") (pin "24") (pinfunction "RTS_24") (pintype "passive"))
      (node (ref "R50") (pin "1") (pinfunction "1_1") (pintype "passive"))
    )
    (net (code "50") (name "Net-(M1-RXD)") (class "Default")
      (node (ref "M1") (pin "22") (pinfunction "RXD_22") (pintype "passive"))
      (node (ref "R51") (pin "1") (pinfunction "1_1") (pintype "passive"))
      (node (ref "R54") (pin "2") (pinfunction "2_2") (pintype "passive"))
    )
    (net (code "51") (name "Net-(M1-SIM_CLK)") (class "Default")
      (node (ref "M1") (pin "30") (pinfunction "SIM_CLK_30") (pintype "passive"))
      (node (ref "R42") (pin "1") (pinfunction "1_1") (pintype "passive"))
    )
    (net (code "52") (name "Net-(M1-SIM_DATA)") (class "Default")
      (node (ref "M1") (pin "29") (pinfunction "SIM_DATA_29") (pintype "passive"))
      (node (ref "R45") (pin "1") (pinfunction "1_1") (pintype "passive"))
    )
    (net (code "53") (name "Net-(M1-SIM_RST)") (class "Default")
      (node (ref "M1") (pin "28") (pinfunction "SIM_RST_28") (pintype "passive"))
      (node (ref "R48") (pin "1") (pinfunction "1_1") (pintype "passive"))
    )
    (net (code "54") (name "Net-(M1-SIM_VDD)") (class "Default")
      (node (ref "C34") (pin "2") (pinfunction "2_2") (pintype "passive"))
      (node (ref "M1") (pin "27") (pinfunction "SIM_VDD_27") (pintype "passive"))
      (node (ref "S2") (pin "1") (pinfunction "VCC_1") (pintype "passive"))
      (node (ref "U18") (pin "5") (pinfunction "Vp_5") (pintype "passive"))
    )
    (net (code "55") (name "Net-(M1-TXD)") (class "Default")
      (node (ref "M1") (pin "21") (pinfunction "TXD_21") (pintype "passive"))
      (node (ref "R52") (pin "1") (pinfunction "1_1") (pintype "passive"))
    )
    (net (code "56") (name "Net-(Q2-B)") (class "Default")
      (node (ref "Q2") (pin "1") (pinfunction "B_1") (pintype "passive"))
      (node (ref "R62") (pin "2") (pinfunction "2_2") (pintype "passive"))
    )
    (net (code "57") (name "Net-(Q2-C)") (class "Default")
      (node (ref "Q2") (pin "3") (pinfunction "C_3") (pintype "passive"))
      (node (ref "SM1") (pin "12") (pinfunction "W1_12") (pintype "passive"))
    )
    (net (code "58") (name "Net-(Q3-B)") (class "Default")
      (node (ref "Q3") (pin "1") (pinfunction "B_1") (pintype "passive"))
      (node (ref "R63") (pin "2") (pinfunction "2_2") (pintype "passive"))
    )
    (net (code "59") (name "Net-(Q3-C)") (class "Default")
      (node (ref "Q3") (pin "3") (pinfunction "C_3") (pintype "passive"))
      (node (ref "SM1") (pin "9") (pinfunction "W2_9") (pintype "passive"))
    )
    (net (code "60") (name "Net-(Q4-B)") (class "Default")
      (node (ref "Q4") (pin "1") (pinfunction "B_1") (pintype "passive"))
      (node (ref "R69") (pin "2") (pinfunction "2_2") (pintype "passive"))
    )
    (net (code "61") (name "Net-(Q4-C)") (class "Default")
      (node (ref "Q4") (pin "3") (pinfunction "C_3") (pintype "passive"))
      (node (ref "SM1") (pin "8") (pinfunction "W3_8") (pintype "passive"))
    )
    (net (code "62") (name "Net-(Q5-B)") (class "Default")
      (node (ref "Q5") (pin "1") (pinfunction "B_1") (pintype "passive"))
      (node (ref "R74") (pin "2") (pinfunction "2_2") (pintype "passive"))
    )
    (net (code "63") (name "Net-(Q5-C)") (class "Default")
      (node (ref "Q5") (pin "3") (pinfunction "C_3") (pintype "passive"))
      (node (ref "SM1") (pin "6") (pinfunction "W4_6") (pintype "passive"))
    )
    (net (code "64") (name "Net-(R73-Pad1)") (class "Default")
      (node (ref "R73") (pin "1") (pinfunction "1_1") (pintype "passive"))
      (node (ref "U21") (pin "7") (pinfunction "Q7_7") (pintype "tri_state"))
    )
    (net (code "65") (name "Net-(S2-CLOCK)") (class "Default")
      (node (ref "C35") (pin "1") (pinfunction "1_1") (pintype "passive"))
      (node (ref "R42") (pin "2") (pinfunction "2_2") (pintype "passive"))
      (node (ref "S2") (pin "3") (pinfunction "CLOCK_3") (pintype "passive"))
      (node (ref "U18") (pin "4") (pinfunction "CH3_4") (pintype "passive"))
    )
    (net (code "66") (name "Net-(S2-DATA)") (class "Default")
      (node (ref "C36") (pin "1") (pinfunction "1_1") (pintype "passive"))
      (node (ref "R45") (pin "2") (pinfunction "2_2") (pintype "passive"))
      (node (ref "S2") (pin "6") (pinfunction "DATA_6") (pintype "passive"))
      (node (ref "U18") (pin "1") (pinfunction "CH1_1") (pintype "passive"))
    )
    (net (code "67") (name "Net-(S2-RESET)") (class "Default")
      (node (ref "C37") (pin "1") (pinfunction "1_1") (pintype "passive"))
      (node (ref "R48") (pin "2") (pinfunction "2_2") (pintype "passive"))
      (node (ref "S2") (pin "2") (pinfunction "RESET_2") (pintype "passive"))
      (node (ref "U18") (pin "3") (pinfunction "CH2_3") (pintype "passive"))
    )
    (net (code "68") (name "Net-(SM1-A)") (class "Default")
      (node (ref "R64") (pin "2") (pinfunction "2_2") (pintype "passive"))
      (node (ref "SM1") (pin "11") (pinfunction "A_11") (pintype "passive"))
    )
    (net (code "69") (name "Net-(SM1-B)") (class "Default")
      (node (ref "R65") (pin "2") (pinfunction "2_2") (pintype "passive"))
      (node (ref "SM1") (pin "7") (pinfunction "B_7") (pintype "passive"))
    )
    (net (code "70") (name "Net-(SM1-C)") (class "Default")
      (node (ref "R66") (pin "2") (pinfunction "2_2") (pintype "passive"))
      (node (ref "SM1") (pin "4") (pinfunction "C_4") (pintype "passive"))
    )
    (net (code "71") (name "Net-(SM1-D)") (class "Default")
      (node (ref "R67") (pin "2") (pinfunction "2_2") (pintype "passive"))
      (node (ref "SM1") (pin "2") (pinfunction "D_2") (pintype "passive"))
    )
    (net (code "72") (name "Net-(SM1-DP)") (class "Default")
      (node (ref "R73") (pin "2") (pinfunction "2_2") (pintype "passive"))
      (node (ref "SM1") (pin "3") (pinfunction "DP_3") (pintype "passive"))
    )
    (net (code "73") (name "Net-(SM1-E)") (class "Default")
      (node (ref "R68") (pin "2") (pinfunction "2_2") (pintype "passive"))
      (node (ref "SM1") (pin "1") (pinfunction "E_1") (pintype "passive"))
    )
    (net (code "74") (name "Net-(SM1-F)") (class "Default")
      (node (ref "R70") (pin "2") (pinfunction "2_2") (pintype "passive"))
      (node (ref "SM1") (pin "10") (pinfunction "F_10") (pintype "passive"))
    )
    (net (code "75") (name "Net-(SM1-G)") (class "Default")
      (node (ref "R72") (pin "2") (pinfunction "2_2") (pintype "passive"))
      (node (ref "SM1") (pin "5") (pinfunction "G_5") (pintype "passive"))
    )
    (net (code "76") (name "Net-(U15-CON)") (class "Default")
      (node (ref "R43") (pin "1") (pinfunction "1_1") (pintype "passive"))
      (node (ref "U15") (pin "5") (pinfunction "CON_5") (pintype "passive"))
      (node (ref "U16") (pin "5") (pinfunction "~{PFO}_5") (pintype "output"))
      (node (ref "U16") (pin "8") (pinfunction "~{WDO}_8") (pintype "output"))
    )
    (net (code "77") (name "Net-(U15-NC)") (class "Default")
      (node (ref "R44") (pin "1") (pinfunction "1_1") (pintype "passive"))
      (node (ref "U15") (pin "4") (pinfunction "NC_4") (pintype "passive"))
      (node (ref "U16") (pin "1") (pinfunction "~{MR}_1") (pintype "input"))
    )
    (net (code "78") (name "Net-(U16-PFI)") (class "Default")
      (node (ref "R47") (pin "1") (pinfunction "1_1") (pintype "passive"))
      (node (ref "R49") (pin "2") (pinfunction "2_2") (pintype "passive"))
      (node (ref "U16") (pin "4") (pinfunction "PFI_4") (pintype "input"))
    )
    (net (code "79") (name "Net-(U17-A3)") (class "Default")
      (node (ref "R56") (pin "2") (pinfunction "2_2") (pintype "passive"))
      (node (ref "U17") (pin "5") (pinfunction "A3_5") (pintype "passive"))
    )
    (net (code "80") (name "Net-(U17-Y1)") (class "Default")
      (node (ref "LED5") (pin "1") (pintype "passive"))
      (node (ref "U17") (pin "2") (pinfunction "Y1_2") (pintype "passive"))
    )
    (net (code "81") (name "Net-(U17-Y2)") (class "Default")
      (node (ref "LED4") (pin "1") (pintype "passive"))
      (node (ref "U17") (pin "4") (pinfunction "Y2_4") (pintype "passive"))
    )
    (net (code "82") (name "Net-(U17-Y3)") (class "Default")
      (node (ref "LED6") (pin "2") (pintype "passive"))
      (node (ref "U17") (pin "6") (pinfunction "Y3_6") (pintype "passive"))
    )
    (net (code "83") (name "Net-(U19-BOOT0)") (class "Default")
      (node (ref "R60") (pin "2") (pinfunction "2_2") (pintype "passive"))
      (node (ref "U19") (pin "60") (pinfunction "BOOT0_60") (pintype "input"))
    )
    (net (code "84") (name "Net-(U19-OSC_IN{slash}CAN_RX{slash}PD0)") (class "Default")
      (node (ref "C47") (pin "1") (pinfunction "1_1") (pintype "passive"))
      (node (ref "U19") (pin "5") (pinfunction "OSC_IN/CAN_RX/PD0_5") (pintype "input"))
      (node (ref "Y1") (pin "2") (pinfunction "2_2") (pintype "passive"))
    )
    (net (code "85") (name "Net-(U19-OSC_OUT{slash}CAN_TX{slash}PD1)") (class "Default")
      (node (ref "C48") (pin "1") (pinfunction "1_1") (pintype "passive"))
      (node (ref "U19") (pin "6") (pinfunction "OSC_OUT/CAN_TX/PD1_6") (pintype "output"))
      (node (ref "Y1") (pin "1") (pinfunction "1_1") (pintype "passive"))
    )
    (net (code "86") (name "Net-(U19-PB2{slash}BOOT1)") (class "Default")
      (node (ref "R61") (pin "1") (pinfunction "1_1") (pintype "passive"))
      (node (ref "U19") (pin "28") (pinfunction "PB2/BOOT1_28") (pintype "bidirectional"))
    )
    (net (code "87") (name "Net-(U21-Q0)") (class "Default")
      (node (ref "R64") (pin "1") (pinfunction "1_1") (pintype "passive"))
      (node (ref "U21") (pin "15") (pinfunction "Q0_15") (pintype "output"))
    )
    (net (code "88") (name "Net-(U21-Q1)") (class "Default")
      (node (ref "R65") (pin "1") (pinfunction "1_1") (pintype "passive"))
      (node (ref "U21") (pin "1") (pinfunction "Q1_1") (pintype "output"))
    )
    (net (code "89") (name "Net-(U21-Q2)") (class "Default")
      (node (ref "R66") (pin "1") (pinfunction "1_1") (pintype "passive"))
      (node (ref "U21") (pin "2") (pinfunction "Q2_2") (pintype "output"))
    )
    (net (code "90") (name "Net-(U21-Q3)") (class "Default")
      (node (ref "R67") (pin "1") (pinfunction "1_1") (pintype "passive"))
      (node (ref "U21") (pin "3") (pinfunction "Q3_3") (pintype "output"))
    )
    (net (code "91") (name "Net-(U21-Q4)") (class "Default")
      (node (ref "R68") (pin "1") (pinfunction "1_1") (pintype "passive"))
      (node (ref "U21") (pin "4") (pinfunction "Q4_4") (pintype "output"))
    )
    (net (code "92") (name "Net-(U21-Q5)") (class "Default")
      (node (ref "R70") (pin "1") (pinfunction "1_1") (pintype "passive"))
      (node (ref "U21") (pin "5") (pinfunction "Q5_5") (pintype "output"))
    )
    (net (code "93") (name "Net-(U21-Q6)") (class "Default")
      (node (ref "R72") (pin "1") (pinfunction "1_1") (pintype "passive"))
      (node (ref "U21") (pin "6") (pinfunction "Q6_6") (pintype "output"))
    )
    (net (code "94") (name "Net-(U22-VDD)") (class "Default")
      (node (ref "C49") (pin "1") (pinfunction "1_1") (pintype "passive"))
      (node (ref "R77") (pin "1") (pinfunction "1_1") (pintype "passive"))
      (node (ref "U22") (pin "6") (pinfunction "VDD_6") (pintype "power_in"))
    )
    (net (code "95") (name "Net-(V1-B)") (class "Default")
      (node (ref "R53") (pin "2") (pinfunction "2_2") (pintype "passive"))
      (node (ref "R55") (pin "1") (pinfunction "1_1") (pintype "passive"))
      (node (ref "V1") (pin "1") (pinfunction "B_1") (pintype "passive"))
    )
    (net (code "96") (name "VCC_3V") (class "Default")
      (node (ref "C32") (pin "1") (pinfunction "1_1") (pintype "passive"))
      (node (ref "C33") (pin "1") (pinfunction "1_1") (pintype "passive"))
      (node (ref "C38") (pin "1") (pinfunction "1_1") (pintype "passive"))
      (node (ref "C39") (pin "1") (pinfunction "1_1") (pintype "passive"))
      (node (ref "C40") (pin "1") (pinfunction "1_1") (pintype "passive"))
      (node (ref "C41") (pin "1") (pinfunction "1_1") (pintype "passive"))
      (node (ref "C42") (pin "1") (pinfunction "1_1") (pintype "passive"))
      (node (ref "C43") (pin "1") (pinfunction "1_1") (pintype "passive"))
      (node (ref "C44") (pin "1") (pinfunction "1_1") (pintype "passive"))
      (node (ref "C45") (pin "1") (pinfunction "1_1") (pintype "passive"))
      (node (ref "C46") (pin "1") (pinfunction "1_1") (pintype "passive"))
      (node (ref "D19") (pin "2") (pintype "passive"))
      (node (ref "J9") (pin "3") (pinfunction "VCC3.3V_3") (pintype "passive"))
      (node (ref "R30") (pin "2") (pinfunction "2_2") (pintype "passive"))
      (node (ref "R43") (pin "2") (pinfunction "2_2") (pintype "passive"))
      (node (ref "R44") (pin "2") (pinfunction "2_2") (pintype "passive"))
      (node (ref "R47") (pin "2") (pinfunction "2_2") (pintype "passive"))
      (node (ref "R57") (pin "1") (pinfunction "1_1") (pintype "passive"))
      (node (ref "R71") (pin "2") (pinfunction "2_2") (pintype "passive"))
      (node (ref "R75") (pin "2") (pinfunction "2_2") (pintype "passive"))
      (node (ref "R76") (pin "2") (pinfunction "2_2") (pintype "passive"))
      (node (ref "R87") (pin "2") (pinfunction "2_2") (pintype "passive"))
      (node (ref "U15") (pin "2") (pinfunction "V+_2") (pintype "passive"))
      (node (ref "U16") (pin "2") (pinfunction "VCC_2") (pintype "power_in"))
      (node (ref "U17") (pin "14") (pinfunction "VCC_14") (pintype "passive"))
      (node (ref "U19") (pin "1") (pinfunction "VBAT_1") (pintype "power_in"))
      (node (ref "U19") (pin "13") (pinfunction "VDDA_13") (pintype "power_in"))
      (node (ref "U19") (pin "19") (pinfunction "VDD_4_19") (pintype "power_in"))
      (node (ref "U19") (pin "32") (pinfunction "VDD_1_32") (pintype "power_in"))
      (node (ref "U19") (pin "48") (pinfunction "VDD_2_48") (pintype "power_in"))
      (node (ref "U19") (pin "64") (pinfunction "VDD_3_64") (pintype "power_in"))
      (node (ref "U20") (pin "3") (pinfunction "~{WP}_3") (pintype "passive"))
      (node (ref "U20") (pin "7") (pinfunction "~{HOLD}_7") (pintype "passive"))
      (node (ref "U20") (pin "8") (pinfunction "VCC_8") (pintype "passive"))
      (node (ref "U21") (pin "10") (pinfunction "~{MR}_10") (pintype "input"))
      (node (ref "U21") (pin "16") (pinfunction "VCC_16") (pintype "power_in"))
    )
    (net (code "97") (name "VCC_4.1V") (class "Default")
      (node (ref "C29") (pin "1") (pinfunction "1_1") (pintype "passive"))
      (node (ref "C30") (pin "1") (pinfunction "1_1") (pintype "passive"))
      (node (ref "C31") (pin "1") (pinfunction "1_1") (pintype "passive"))
      (node (ref "EC6") (pin "1") (pinfunction "1_1") (pintype "passive"))
      (node (ref "M1") (pin "33") (pinfunction "VBAT_33") (pintype "passive"))
      (node (ref "M1") (pin "34") (pinfunction "VBAT_34") (pintype "passive"))
    )
    (net (code "98") (name "unconnected-(J9-NC-Pad1)") (class "Default")
      (node (ref "J9") (pin "1") (pinfunction "NC_1") (pintype "passive"))
    )
    (net (code "99") (name "unconnected-(M1-AGND-Pad1)") (class "Default")
      (node (ref "M1") (pin "1") (pinfunction "AGND_1") (pintype "passive+no_connect"))
    )
    (net (code "100") (name "unconnected-(M1-CTS-Pad23)") (class "Default")
      (node (ref "M1") (pin "23") (pinfunction "CTS_23") (pintype "passive+no_connect"))
    )
    (net (code "101") (name "unconnected-(M1-DBG_RXD-Pad14)") (class "Default")
      (node (ref "M1") (pin "14") (pinfunction "DBG_RXD_14") (pintype "passive"))
    )
    (net (code "102") (name "unconnected-(M1-DBG_TXD-Pad15)") (class "Default")
      (node (ref "M1") (pin "15") (pinfunction "DBG_TXD_15") (pintype "passive"))
    )
    (net (code "103") (name "unconnected-(M1-DCD-Pad25)") (class "Default")
      (node (ref "M1") (pin "25") (pinfunction "DCD_25") (pintype "passive+no_connect"))
    )
    (net (code "104") (name "unconnected-(M1-DTR-Pad20)") (class "Default")
      (node (ref "M1") (pin "20") (pinfunction "DTR_20") (pintype "passive+no_connect"))
    )
    (net (code "105") (name "unconnected-(M1-EMERG_OFF-Pad11)") (class "Default")
      (node (ref "M1") (pin "11") (pinfunction "EMERG_OFF_11") (pintype "passive+no_connect"))
    )
    (net (code "106") (name "unconnected-(M1-LOUDSPKN-Pad8)") (class "Default")
      (node (ref "M1") (pin "8") (pinfunction "LOUDSPKN_8") (pintype "passive+no_connect"))
    )
    (net (code "107") (name "unconnected-(M1-LOUDSPKP-Pad9)") (class "Default")
      (node (ref "M1") (pin "9") (pinfunction "LOUDSPKP_9") (pintype "passive+no_connect"))
    )
    (net (code "108") (name "unconnected-(M1-MIC1N-Pad5)") (class "Default")
      (node (ref "M1") (pin "5") (pinfunction "MIC1N_5") (pintype "passive+no_connect"))
    )
    (net (code "109") (name "unconnected-(M1-MIC1P-Pad4)") (class "Default")
      (node (ref "M1") (pin "4") (pinfunction "MIC1P_4") (pintype "passive+no_connect"))
    )
    (net (code "110") (name "unconnected-(M1-MIC2N-Pad3)") (class "Default")
      (node (ref "M1") (pin "3") (pinfunction "MIC2N_3") (pintype "passive+no_connect"))
    )
    (net (code "111") (name "unconnected-(M1-MIC2P-Pad2)") (class "Default")
      (node (ref "M1") (pin "2") (pinfunction "MIC2P_2") (pintype "passive+no_connect"))
    )
    (net (code "112") (name "unconnected-(M1-RESERVED-Pad16)") (class "Default")
      (node (ref "M1") (pin "16") (pinfunction "RESERVED_16") (pintype "passive"))
    )
    (net (code "113") (name "unconnected-(M1-RESERVED-Pad17)") (class "Default")
      (node (ref "M1") (pin "17") (pinfunction "RESERVED_17") (pintype "passive"))
    )
    (net (code "114") (name "unconnected-(M1-RESERVED-Pad18)") (class "Default")
      (node (ref "M1") (pin "18") (pinfunction "RESERVED_18") (pintype "passive"))
    )
    (net (code "115") (name "unconnected-(M1-RESERVED-Pad41)") (class "Default")
      (node (ref "M1") (pin "41") (pinfunction "RESERVED_41") (pintype "passive"))
    )
    (net (code "116") (name "unconnected-(M1-RESERVED-Pad42)") (class "Default")
      (node (ref "M1") (pin "42") (pinfunction "RESERVED_42") (pintype "passive"))
    )
    (net (code "117") (name "unconnected-(M1-RI-Pad26)") (class "Default")
      (node (ref "M1") (pin "26") (pinfunction "RI_26") (pintype "passive"))
    )
    (net (code "118") (name "unconnected-(M1-SPK1N-Pad6)") (class "Default")
      (node (ref "M1") (pin "6") (pinfunction "SPK1N_6") (pintype "passive+no_connect"))
    )
    (net (code "119") (name "unconnected-(M1-SPK1P-Pad7)") (class "Default")
      (node (ref "M1") (pin "7") (pinfunction "SPK1P_7") (pintype "passive+no_connect"))
    )
    (net (code "120") (name "unconnected-(M1-VDD_EXT-Pad19)") (class "Default")
      (node (ref "M1") (pin "19") (pinfunction "VDD_EXT_19") (pintype "passive"))
    )
    (net (code "121") (name "unconnected-(M1-VRTC-Pad32)") (class "Default")
      (node (ref "M1") (pin "32") (pinfunction "VRTC_32") (pintype "passive"))
    )
    (net (code "122") (name "unconnected-(S2-TLINK+-Pad7)") (class "Default")
      (node (ref "S2") (pin "7") (pinfunction "TLINK+_7") (pintype "passive"))
    )
    (net (code "123") (name "unconnected-(S2-TLINK--Pad8)") (class "Default")
      (node (ref "S2") (pin "8") (pinfunction "TLINK-_8") (pintype "passive"))
    )
    (net (code "124") (name "unconnected-(S2-VPP-Pad5)") (class "Default")
      (node (ref "S2") (pin "5") (pinfunction "VPP_5") (pintype "passive"))
    )
    (net (code "125") (name "unconnected-(U15-NO-Pad6)") (class "Default")
      (node (ref "U15") (pin "6") (pinfunction "NO_6") (pintype "passive"))
    )
    (net (code "126") (name "unconnected-(U17-Y4-Pad8)") (class "Default")
      (node (ref "U17") (pin "8") (pinfunction "Y4_8") (pintype "passive"))
    )
    (net (code "127") (name "unconnected-(U17-Y5-Pad10)") (class "Default")
      (node (ref "U17") (pin "10") (pinfunction "Y5_10") (pintype "passive"))
    )
    (net (code "128") (name "unconnected-(U17-Y6-Pad12)") (class "Default")
      (node (ref "U17") (pin "12") (pinfunction "Y6_12") (pintype "passive"))
    )
    (net (code "129") (name "unconnected-(U18-CH4-Pad6)") (class "Default")
      (node (ref "U18") (pin "6") (pinfunction "CH4_6") (pintype "passive"))
    )
    (net (code "130") (name "unconnected-(U19-PA0{slash}USART2_CTS{slash}ADC123_IN0-Pad14)") (class "Default")
      (node (ref "U19") (pin "14") (pinfunction "PA0/USART2_CTS/ADC123_IN0_14") (pintype "bidirectional"))
    )
    (net (code "131") (name "unconnected-(U19-PA8{slash}USART1_CK-Pad41)") (class "Default")
      (node (ref "U19") (pin "41") (pinfunction "PA8/USART1_CK_41") (pintype "bidirectional"))
    )
    (net (code "132") (name "unconnected-(U19-PA9{slash}USART1_TX-Pad42)") (class "Default")
      (node (ref "U19") (pin "42") (pinfunction "PA9/USART1_TX_42") (pintype "bidirectional"))
    )
    (net (code "133") (name "unconnected-(U19-PA10{slash}USART1_RX-Pad43)") (class "Default")
      (node (ref "U19") (pin "43") (pinfunction "PA10/USART1_RX_43") (pintype "bidirectional"))
    )
    (net (code "134") (name "unconnected-(U19-PB0{slash}ADC12_IN8-Pad26)") (class "Default")
      (node (ref "U19") (pin "26") (pinfunction "PB0/ADC12_IN8_26") (pintype "bidirectional"))
    )
    (net (code "135") (name "unconnected-(U19-PB13{slash}SPI2_SCK{slash}USART3_CTS-Pad34)") (class "Default")
      (node (ref "U19") (pin "34") (pinfunction "PB13/SPI2_SCK/USART3_CTS_34") (pintype "bidirectional"))
    )
    (net (code "136") (name "unconnected-(U19-PB14{slash}SPI2_MISO{slash}USART3_RTS-Pad35)") (class "Default")
      (node (ref "U19") (pin "35") (pinfunction "PB14/SPI2_MISO/USART3_RTS_35") (pintype "bidirectional"))
    )
    (net (code "137") (name "unconnected-(U19-PB15{slash}SPI2_MOSI-Pad36)") (class "Default")
      (node (ref "U19") (pin "36") (pinfunction "PB15/SPI2_MOSI_36") (pintype "bidirectional"))
    )
    (net (code "138") (name "unconnected-(U19-PC0{slash}ADC123_IN10-Pad8)") (class "Default")
      (node (ref "U19") (pin "8") (pinfunction "PC0/ADC123_IN10_8") (pintype "bidirectional"))
    )
    (net (code "139") (name "unconnected-(U19-PC13-TAMPER-RTC-Pad2)") (class "Default")
      (node (ref "U19") (pin "2") (pinfunction "PC13-TAMPER-RTC_2") (pintype "bidirectional"))
    )
    (net (code "140") (name "unconnected-(U19-PC14-OSC32_IN-Pad3)") (class "Default")
      (node (ref "U19") (pin "3") (pinfunction "PC14-OSC32_IN_3") (pintype "bidirectional"))
    )
    (net (code "141") (name "unconnected-(U19-PC15-OSC32_OUT-Pad4)") (class "Default")
      (node (ref "U19") (pin "4") (pinfunction "PC15-OSC32_OUT_4") (pintype "bidirectional"))
    )
    (net (code "142") (name "unconnected-(U21-Q7-Pad9)") (class "Default")
      (node (ref "U21") (pin "9") (pinfunction "Q7_9") (pintype "output"))
    )
    (net (code "143") (name "unconnected-(U22-FOE-Pad7)") (class "Default")
      (node (ref "U22") (pin "7") (pinfunction "FOE_7") (pintype "input+no_connect"))
    )
    (net (code "144") (name "unconnected-(U22-FOUT-Pad3)") (class "Default")
      (node (ref "U22") (pin "3") (pinfunction "FOUT_3") (pintype "output+no_connect"))
    )
    (net (code "145") (name "unconnected-(U22-~{INTA}-Pad10)") (class "Default")
      (node (ref "U22") (pin "10") (pinfunction "~{INTA}_10") (pintype "open_collector+no_connect"))
    )
    (net (code "146") (name "unconnected-(U22-~{INT}B-Pad12)") (class "Default")
      (node (ref "U22") (pin "12") (pinfunction "~{INT}B_12") (pintype "passive+no_connect"))
    )
  )
)
